# Final_Project_IOH.net
KiCad netlist of a schematic drawn in EAGLE
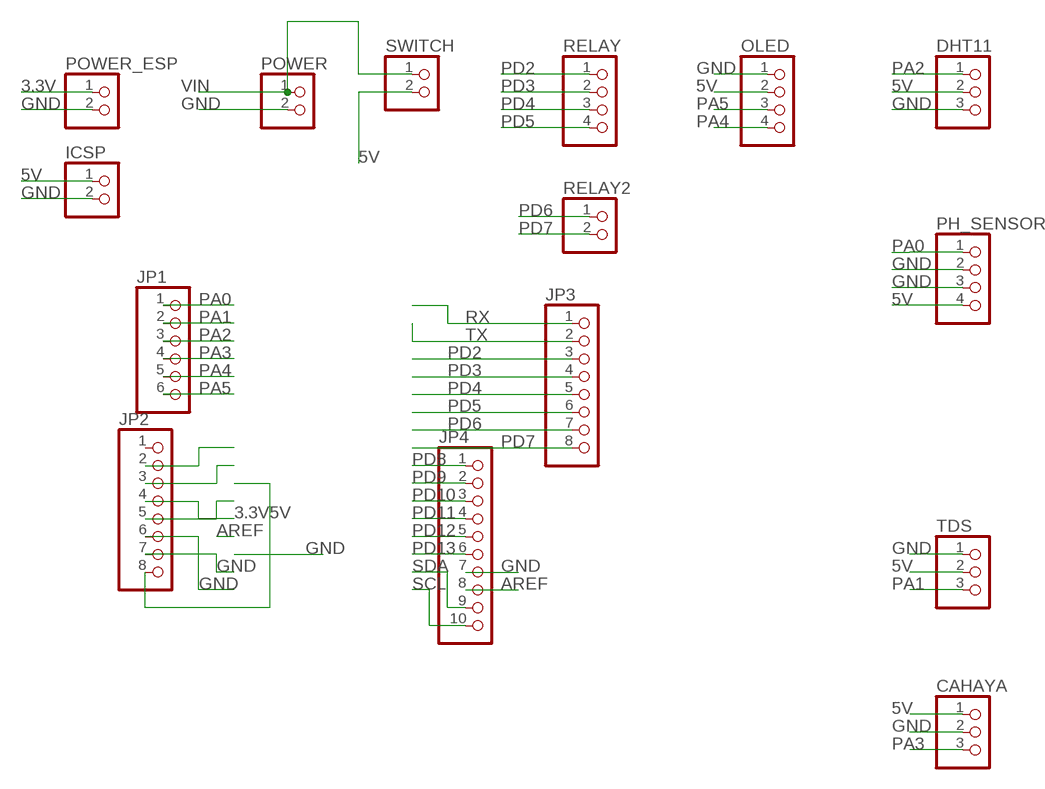
[diagram p0: schematic, sheet 1]

(export (version "E")
  (design (tool "Eeschema 10.0.6"))
  (components
    (comp (ref "CAHAYA")
      (value "PINHD-1X3")
      (footprint "eagle-import:1X03")
      (libsource (lib "eagle-import") (part "PINHD-1X3"))
    )
    (comp (ref "DHT11")
      (value "PINHD-1X3")
      (footprint "eagle-import:1X03")
      (libsource (lib "eagle-import") (part "PINHD-1X3"))
    )
    (comp (ref "ICSP")
      (value "PINHD-1X2")
      (footprint "eagle-import:1X02")
      (libsource (lib "eagle-import") (part "PINHD-1X2"))
    )
    (comp (ref "JP1")
      (value "PINHD-1X6")
      (footprint "eagle-import:1X06")
      (libsource (lib "eagle-import") (part "PINHD-1X6"))
    )
    (comp (ref "JP2")
      (value "PINHD-1X8")
      (footprint "eagle-import:1X08")
      (libsource (lib "eagle-import") (part "PINHD-1X8"))
    )
    (comp (ref "JP3")
      (value "PINHD-1X8")
      (footprint "eagle-import:1X08")
      (libsource (lib "eagle-import") (part "PINHD-1X8"))
    )
    (comp (ref "JP4")
      (value "PINHD-1X10")
      (footprint "eagle-import:1X10")
      (libsource (lib "eagle-import") (part "PINHD-1X10"))
    )
    (comp (ref "OLED")
      (value "PINHD-1X4")
      (footprint "eagle-import:1X04")
      (libsource (lib "eagle-import") (part "PINHD-1X4"))
    )
    (comp (ref "PH_SENSOR")
      (value "PINHD-1X4")
      (footprint "eagle-import:1X04")
      (libsource (lib "eagle-import") (part "PINHD-1X4"))
    )
    (comp (ref "POWER")
      (value "PINHD-1X2")
      (footprint "eagle-import:1X02")
      (libsource (lib "eagle-import") (part "PINHD-1X2"))
    )
    (comp (ref "POWER_ESP")
      (value "PINHD-1X2")
      (footprint "eagle-import:1X02")
      (libsource (lib "eagle-import") (part "PINHD-1X2"))
    )
    (comp (ref "RELAY")
      (value "PINHD-1X4")
      (footprint "eagle-import:1X04")
      (libsource (lib "eagle-import") (part "PINHD-1X4"))
    )
    (comp (ref "RELAY2")
      (value "PINHD-1X2")
      (footprint "eagle-import:1X02")
      (libsource (lib "eagle-import") (part "PINHD-1X2"))
    )
    (comp (ref "SWITCH")
      (value "PINHD-1X2")
      (footprint "eagle-import:1X02")
      (libsource (lib "eagle-import") (part "PINHD-1X2"))
    )
    (comp (ref "TDS")
      (value "PINHD-1X3")
      (footprint "eagle-import:1X03")
      (libsource (lib "eagle-import") (part "PINHD-1X3"))
    )
  )
  (nets
    (net (code "1") (name "3.3V") (class "Default")
      (node (ref "JP2") (pin "4") (pinfunction "4_4") (pintype "passive"))
      (node (ref "POWER_ESP") (pin "1") (pinfunction "1_1") (pintype "passive"))
    )
    (net (code "2") (name "5V") (class "Default")
      (node (ref "CAHAYA") (pin "1") (pinfunction "1_1") (pintype "passive"))
      (node (ref "DHT11") (pin "2") (pinfunction "2_2") (pintype "passive"))
      (node (ref "ICSP") (pin "1") (pinfunction "1_1") (pintype "passive"))
      (node (ref "JP2") (pin "8") (pinfunction "8_8") (pintype "passive"))
      (node (ref "OLED") (pin "2") (pinfunction "2_2") (pintype "passive"))
      (node (ref "PH_SENSOR") (pin "4") (pinfunction "4_4") (pintype "passive"))
      (node (ref "SWITCH") (pin "2") (pinfunction "2_2") (pintype "passive"))
      (node (ref "TDS") (pin "2") (pinfunction "2_2") (pintype "passive"))
    )
    (net (code "3") (name "AREF") (class "Default")
      (node (ref "JP4") (pin "8") (pinfunction "8_8") (pintype "passive"))
    )
    (net (code "4") (name "GND") (class "Default")
      (node (ref "CAHAYA") (pin "2") (pinfunction "2_2") (pintype "passive"))
      (node (ref "DHT11") (pin "3") (pinfunction "3_3") (pintype "passive"))
      (node (ref "ICSP") (pin "2") (pinfunction "2_2") (pintype "passive"))
      (node (ref "JP2") (pin "6") (pinfunction "6_6") (pintype "passive"))
      (node (ref "JP2") (pin "7") (pinfunction "7_7") (pintype "passive"))
      (node (ref "JP4") (pin "7") (pinfunction "7_7") (pintype "passive"))
      (node (ref "OLED") (pin "1") (pinfunction "1_1") (pintype "passive"))
      (node (ref "PH_SENSOR") (pin "2") (pinfunction "2_2") (pintype "passive"))
      (node (ref "PH_SENSOR") (pin "3") (pinfunction "3_3") (pintype "passive"))
      (node (ref "POWER") (pin "2") (pinfunction "2_2") (pintype "passive"))
      (node (ref "POWER_ESP") (pin "2") (pinfunction "2_2") (pintype "passive"))
      (node (ref "TDS") (pin "1") (pinfunction "1_1") (pintype "passive"))
    )
    (net (code "5") (name "PA0") (class "Default")
      (node (ref "JP1") (pin "1") (pinfunction "1_1") (pintype "passive"))
      (node (ref "PH_SENSOR") (pin "1") (pinfunction "1_1") (pintype "passive"))
    )
    (net (code "6") (name "PA1") (class "Default")
      (node (ref "JP1") (pin "2") (pinfunction "2_2") (pintype "passive"))
      (node (ref "TDS") (pin "3") (pinfunction "3_3") (pintype "passive"))
    )
    (net (code "7") (name "PA2") (class "Default")
      (node (ref "DHT11") (pin "1") (pinfunction "1_1") (pintype "passive"))
      (node (ref "JP1") (pin "3") (pinfunction "3_3") (pintype "passive"))
    )
    (net (code "8") (name "PA3") (class "Default")
      (node (ref "CAHAYA") (pin "3") (pinfunction "3_3") (pintype "passive"))
      (node (ref "JP1") (pin "4") (pinfunction "4_4") (pintype "passive"))
    )
    (net (code "9") (name "PA4") (class "Default")
      (node (ref "JP1") (pin "5") (pinfunction "5_5") (pintype "passive"))
      (node (ref "OLED") (pin "4") (pinfunction "4_4") (pintype "passive"))
    )
    (net (code "10") (name "PA5") (class "Default")
      (node (ref "JP1") (pin "6") (pinfunction "6_6") (pintype "passive"))
      (node (ref "OLED") (pin "3") (pinfunction "3_3") (pintype "passive"))
    )
    (net (code "11") (name "PD2") (class "Default")
      (node (ref "JP3") (pin "3") (pinfunction "3_3") (pintype "passive"))
      (node (ref "RELAY") (pin "1") (pinfunction "1_1") (pintype "passive"))
    )
    (net (code "12") (name "PD3") (class "Default")
      (node (ref "JP3") (pin "4") (pinfunction "4_4") (pintype "passive"))
      (node (ref "RELAY") (pin "2") (pinfunction "2_2") (pintype "passive"))
    )
    (net (code "13") (name "PD4") (class "Default")
      (node (ref "JP3") (pin "5") (pinfunction "5_5") (pintype "passive"))
      (node (ref "RELAY") (pin "3") (pinfunction "3_3") (pintype "passive"))
    )
    (net (code "14") (name "PD5") (class "Default")
      (node (ref "JP3") (pin "6") (pinfunction "6_6") (pintype "passive"))
      (node (ref "RELAY") (pin "4") (pinfunction "4_4") (pintype "passive"))
    )
    (net (code "15") (name "PD6") (class "Default")
      (node (ref "JP3") (pin "7") (pinfunction "7_7") (pintype "passive"))
      (node (ref "RELAY2") (pin "1") (pinfunction "1_1") (pintype "passive"))
    )
    (net (code "16") (name "PD7") (class "Default")
      (node (ref "JP3") (pin "8") (pinfunction "8_8") (pintype "passive"))
      (node (ref "RELAY2") (pin "2") (pinfunction "2_2") (pintype "passive"))
    )
    (net (code "17") (name "PD8") (class "Default")
      (node (ref "JP4") (pin "1") (pinfunction "1_1") (pintype "passive"))
    )
    (net (code "18") (name "PD9") (class "Default")
      (node (ref "JP4") (pin "2") (pinfunction "2_2") (pintype "passive"))
    )
    (net (code "19") (name "PD10") (class "Default")
      (node (ref "JP4") (pin "3") (pinfunction "3_3") (pintype "passive"))
    )
    (net (code "20") (name "PD11") (class "Default")
      (node (ref "JP4") (pin "4") (pinfunction "4_4") (pintype "passive"))
    )
    (net (code "21") (name "PD12") (class "Default")
      (node (ref "JP4") (pin "5") (pinfunction "5_5") (pintype "passive"))
    )
    (net (code "22") (name "PD13") (class "Default")
      (node (ref "JP4") (pin "6") (pinfunction "6_6") (pintype "passive"))
    )
    (net (code "23") (name "RX") (class "Default")
      (node (ref "JP3") (pin "1") (pinfunction "1_1") (pintype "passive"))
    )
    (net (code "24") (name "SCL") (class "Default")
      (node (ref "JP4") (pin "10") (pinfunction "10_10") (pintype "passive"))
    )
    (net (code "25") (name "SDA") (class "Default")
      (node (ref "JP4") (pin "9") (pinfunction "9_9") (pintype "passive"))
    )
    (net (code "26") (name "TX") (class "Default")
      (node (ref "JP3") (pin "2") (pinfunction "2_2") (pintype "passive"))
    )
    (net (code "27") (name "VIN") (class "Default")
      (node (ref "POWER") (pin "1") (pinfunction "1_1") (pintype "passive"))
      (node (ref "SWITCH") (pin "1") (pinfunction "1_1") (pintype "passive"))
    )
    (net (code "28") (name "unconnected-(JP2-Pad1)") (class "Default")
      (node (ref "JP2") (pin "1") (pinfunction "1_1") (pintype "passive"))
    )
    (net (code "29") (name "unconnected-(JP2-Pad2)") (class "Default")
      (node (ref "JP2") (pin "2") (pinfunction "2_2") (pintype "passive"))
    )
    (net (code "30") (name "unconnected-(JP2-Pad3)") (class "Default")
      (node (ref "JP2") (pin "3") (pinfunction "3_3") (pintype "passive"))
    )
    (net (code "31") (name "unconnected-(JP2-Pad5)") (class "Default")
      (node (ref "JP2") (pin "5") (pinfunction "5_5") (pintype "passive"))
    )
  )
)
